# pixel-power-injection-v1b.net
KiCad netlist of a schematic drawn in EAGLE
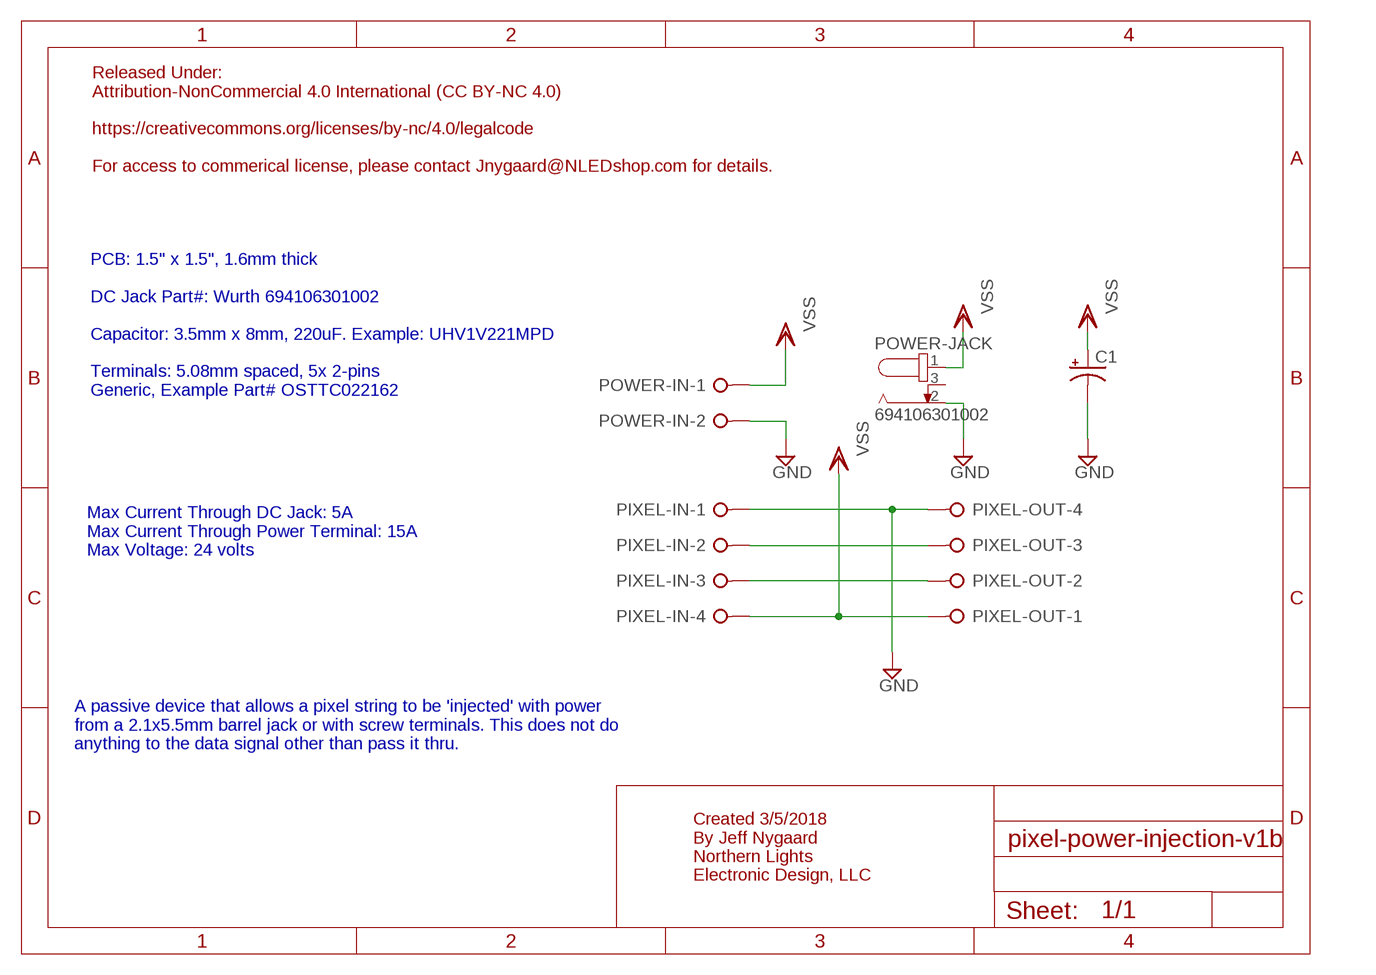
[diagram p0: schematic, sheet 1]

(export (version "E")
  (design (tool "Eeschema 10.0.6"))
  (components
    (comp (ref "C1")
      (value "CPOL-USE3.5-8")
      (footprint "eagle-import:E3,5-8")
      (libsource (lib "eagle-import") (part "CPOL-USE3.5-8"))
    )
    (comp (ref "PIXEL-IN")
      (value "W237-04P")
      (footprint "eagle-import:W237-4P")
      (libsource (lib "eagle-import") (part "W237-04P"))
    )
    (comp (ref "PIXEL-OUT")
      (value "W237-04P")
      (footprint "eagle-import:W237-4P")
      (libsource (lib "eagle-import") (part "W237-04P"))
    )
    (comp (ref "POWER-IN")
      (value "W237-02P")
      (footprint "eagle-import:W237-132")
      (libsource (lib "eagle-import") (part "W237-02P"))
    )
    (comp (ref "POWER-JACK")
      (value "694106301002")
      (footprint "eagle-import:694106301002")
      (libsource (lib "eagle-import") (part "694106301002"))
    )
  )
  (nets
    (net (code "1") (name "GND") (class "Default")
      (node (ref "C1") (pin "-") (pinfunction "-_-") (pintype "passive"))
      (node (ref "PIXEL-IN") (pin "1") (pinfunction "KL_1") (pintype "passive"))
      (node (ref "PIXEL-OUT") (pin "4") (pinfunction "KL_4") (pintype "passive"))
      (node (ref "POWER-IN") (pin "2") (pinfunction "KL_2") (pintype "passive"))
      (node (ref "POWER-JACK") (pin "2") (pinfunction "2_2") (pintype "passive"))
    )
    (net (code "2") (name "Net-(PIXEL-INB-KL)") (class "Default")
      (node (ref "PIXEL-IN") (pin "2") (pinfunction "KL_2") (pintype "passive"))
      (node (ref "PIXEL-OUT") (pin "3") (pinfunction "KL_3") (pintype "passive"))
    )
    (net (code "3") (name "Net-(PIXEL-INC-KL)") (class "Default")
      (node (ref "PIXEL-IN") (pin "3") (pinfunction "KL_3") (pintype "passive"))
      (node (ref "PIXEL-OUT") (pin "2") (pinfunction "KL_2") (pintype "passive"))
    )
    (net (code "4") (name "VSS") (class "Default")
      (node (ref "C1") (pin "+") (pinfunction "+_+") (pintype "passive"))
      (node (ref "PIXEL-IN") (pin "4") (pinfunction "KL_4") (pintype "passive"))
      (node (ref "PIXEL-OUT") (pin "1") (pinfunction "KL_1") (pintype "passive"))
      (node (ref "POWER-IN") (pin "1") (pinfunction "KL_1") (pintype "passive"))
      (node (ref "POWER-JACK") (pin "1") (pinfunction "1_1") (pintype "passive"))
    )
    (net (code "5") (name "unconnected-(POWER-JACK-Pad3)") (class "Default")
      (node (ref "POWER-JACK") (pin "3") (pinfunction "3_3") (pintype "passive"))
    )
  )
)
